# stm32.net
KiCad netlist of a schematic drawn in Altium Designer
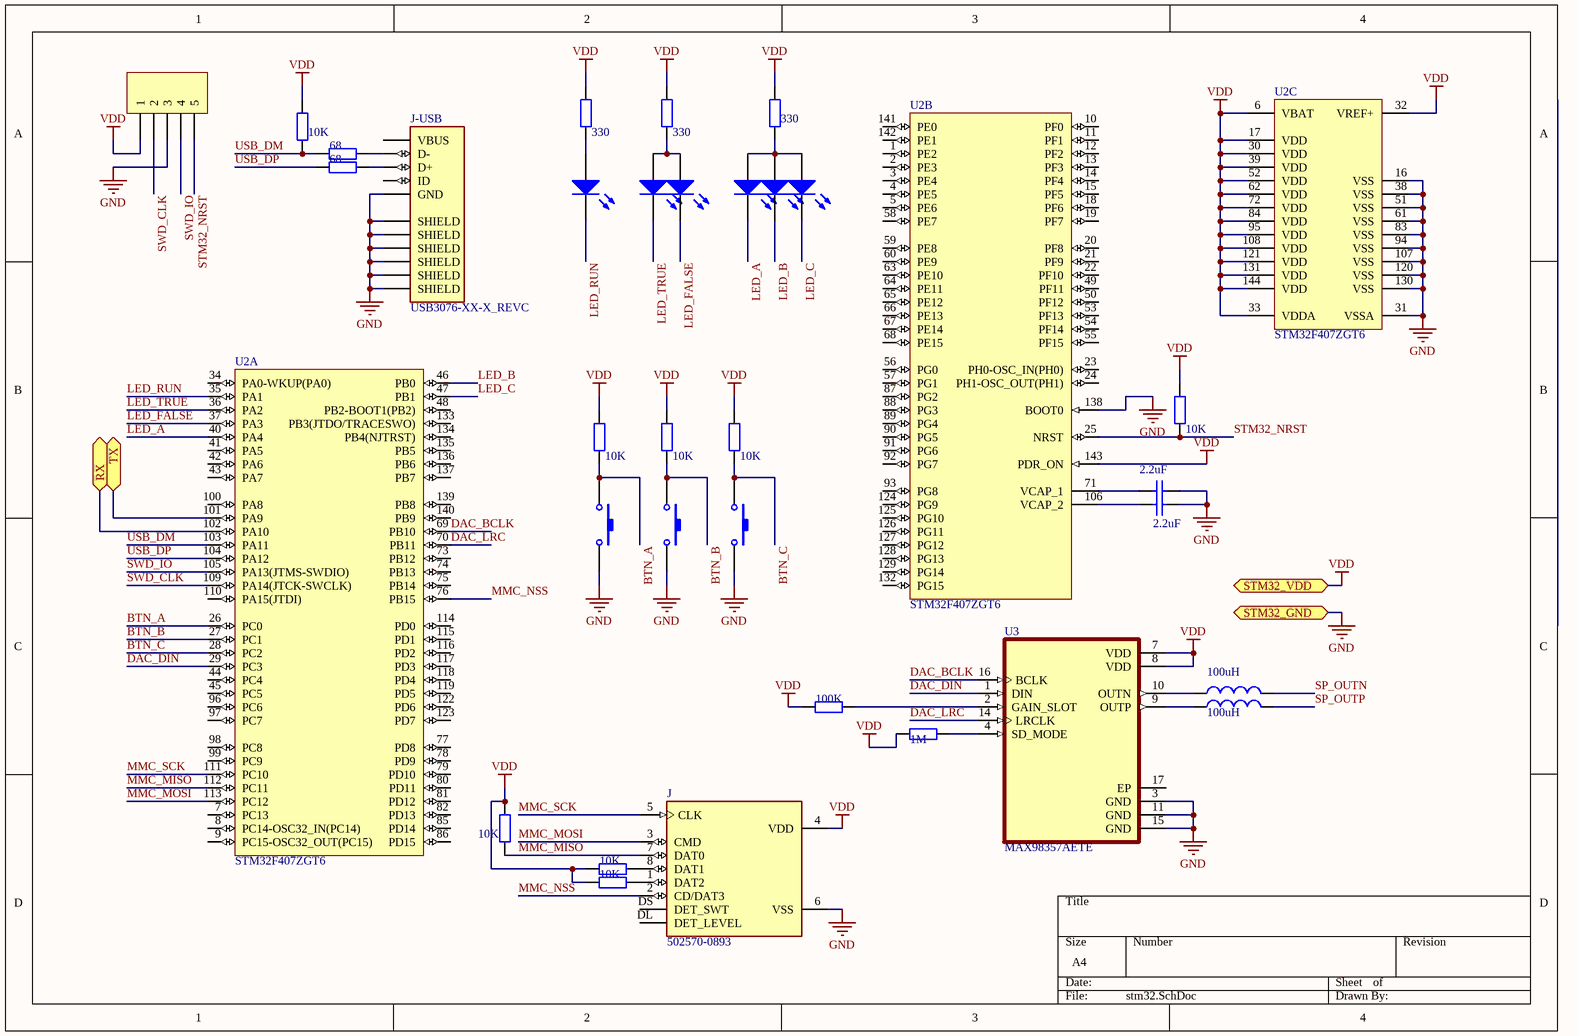
[diagram p0: stm32.SchDoc]

(export (version "E")
  (design (tool "Eeschema 10.0.6"))
  (components
    (comp (ref "D-BTN1")
      (value "LED0")
      (footprint "LED-0")
      (description "Typical INFRARED GaAs LED")
      (fields (field (name "PUBLISHER") "Altium Limited"))
      (libsource (lib "Miscellaneous Devices") (part "LED0"))
    )
    (comp (ref "D-BTN2")
      (value "LED0")
      (footprint "LED-0")
      (description "Typical INFRARED GaAs LED")
      (fields (field (name "PUBLISHER") "Altium Limited"))
      (libsource (lib "Miscellaneous Devices") (part "LED0"))
    )
    (comp (ref "D-BTN3")
      (value "LED0")
      (footprint "LED-0")
      (description "Typical INFRARED GaAs LED")
      (fields (field (name "PUBLISHER") "Altium Limited"))
      (libsource (lib "Miscellaneous Devices") (part "LED0"))
    )
    (comp (ref "D-LED-ANS1")
      (value "LED0")
      (footprint "LED-0")
      (description "Typical INFRARED GaAs LED")
      (fields (field (name "PUBLISHER") "Altium Limited"))
      (libsource (lib "Miscellaneous Devices") (part "LED0"))
    )
    (comp (ref "D-LED-ANS2")
      (value "LED0")
      (footprint "LED-0")
      (description "Typical INFRARED GaAs LED")
      (fields (field (name "PUBLISHER") "Altium Limited"))
      (libsource (lib "Miscellaneous Devices") (part "LED0"))
    )
    (comp (ref "D2")
      (value "LED0")
      (footprint "LED-0")
      (description "Typical INFRARED GaAs LED")
      (fields (field (name "PUBLISHER") "Altium Limited"))
      (libsource (lib "Miscellaneous Devices") (part "LED0"))
    )
    (comp (ref "J")
      (value "502570-0893")
      (footprint "MOLEX_502570-0893")
      (description "10 _8 + 2_ Position Card Connector Secure Digital - microSDâ„¢ Surface Mount, Right Angle Gold")
      (fields (field (name "MF") "Molex"))
      (libsource (lib "MMC-502570-0893") (part "502570-0893"))
    )
    (comp (ref "J-USB")
      (value "USB3076-XX-X_REVC")
      (footprint "GCT_USB3076-XX-X_REVC")
      (description "USB - micro B USB 2.0 Receptacle Connector 5 Position Surface Mount, Right Angle; Through Hole")
      (fields (field (name "MP") "USB3076-30-A") (field (name "MF") "Global Connector Technology"))
      (libsource (lib "USB3076-XX-X_REVC") (part "USB3076-XX-X_REVC"))
    )
    (comp (ref "L-DAC1")
      (value "100uH")
      (footprint "0402-A")
      (description "Inductor")
      (fields (field (name "PUBLISHER") "Altium Limited"))
      (libsource (lib "Miscellaneous Devices") (part "Inductor"))
    )
    (comp (ref "L-DAC2")
      (value "100uH")
      (footprint "0402-A")
      (description "Inductor")
      (fields (field (name "PUBLISHER") "Altium Limited"))
      (libsource (lib "Miscellaneous Devices") (part "Inductor"))
    )
    (comp (ref "P-STM32PROG")
      (value "Header 5")
      (footprint "HDR1X5")
      (description "Header, 5-Pin")
      (fields (field (name "PUBLISHER") "Altium Limited"))
      (libsource (lib "Miscellaneous Connectors") (part "Header 5"))
    )
    (comp (ref "R-BTN1")
      (value "10K")
      (footprint "AXIAL-0.4")
      (description "Resistor")
      (fields (field (name "Comment") "Res2") (field (name "PUBLISHER") "Altium Limited"))
      (libsource (lib "") (part "Res2_1"))
    )
    (comp (ref "R-BTN2")
      (value "10K")
      (footprint "AXIAL-0.4")
      (description "Resistor")
      (fields (field (name "Comment") "Res2") (field (name "PUBLISHER") "Altium Limited"))
      (libsource (lib "") (part "Res2_1"))
    )
    (comp (ref "R-BTN3")
      (value "10K")
      (footprint "AXIAL-0.4")
      (description "Resistor")
      (fields (field (name "Comment") "Res2") (field (name "PUBLISHER") "Altium Limited"))
      (libsource (lib "") (part "Res2_1"))
    )
    (comp (ref "R-DAC1")
      (value "100K")
      (footprint "AXIAL-0.4")
      (description "Resistor")
      (fields (field (name "Comment") "Res2") (field (name "PUBLISHER") "Altium Limited"))
      (libsource (lib "") (part "Res2_2"))
    )
    (comp (ref "R-DAC3")
      (value "1M")
      (footprint "AXIAL-0.4")
      (description "Resistor")
      (fields (field (name "Comment") "Res2") (field (name "PUBLISHER") "Altium Limited"))
      (libsource (lib "") (part "Res2_2"))
    )
    (comp (ref "R-LED-ANS1")
      (value "330")
      (footprint "AXIAL-0.4")
      (description "Resistor")
      (fields (field (name "Comment") "Res2") (field (name "PUBLISHER") "Altium Limited"))
      (libsource (lib "Miscellaneous Devices") (part "Res2"))
    )
    (comp (ref "R-LED-BTN1")
      (value "330")
      (footprint "AXIAL-0.4")
      (description "Resistor")
      (fields (field (name "Comment") "Res2") (field (name "PUBLISHER") "Altium Limited"))
      (libsource (lib "Miscellaneous Devices") (part "Res2"))
    )
    (comp (ref "R-LED-RUN1")
      (value "330")
      (footprint "AXIAL-0.4")
      (description "Resistor")
      (fields (field (name "Comment") "Res2") (field (name "PUBLISHER") "Altium Limited"))
      (libsource (lib "Miscellaneous Devices") (part "Res2"))
    )
    (comp (ref "R-MMC1")
      (value "10K")
      (footprint "AXIAL-0.4")
      (description "Resistor")
      (fields (field (name "Comment") "Res2") (field (name "PUBLISHER") "Altium Limited"))
      (libsource (lib "Miscellaneous Devices") (part "Res2"))
    )
    (comp (ref "R-MMC2")
      (value "10K")
      (footprint "AXIAL-0.4")
      (description "Resistor")
      (fields (field (name "Comment") "Res2") (field (name "PUBLISHER") "Altium Limited"))
      (libsource (lib "") (part "Res2_2"))
    )
    (comp (ref "R-MMC3")
      (value "10K")
      (footprint "AXIAL-0.4")
      (description "Resistor")
      (fields (field (name "Comment") "Res2") (field (name "PUBLISHER") "Altium Limited"))
      (libsource (lib "") (part "Res2_2"))
    )
    (comp (ref "R-STM1")
      (value "10K")
      (footprint "AXIAL-0.4")
      (description "Resistor")
      (fields (field (name "Comment") "Res2") (field (name "PUBLISHER") "Altium Limited"))
      (libsource (lib "Miscellaneous Devices") (part "Res2"))
    )
    (comp (ref "R-USB1")
      (value "10K")
      (footprint "AXIAL-0.4")
      (description "Resistor")
      (fields (field (name "Comment") "Res2") (field (name "PUBLISHER") "Altium Limited"))
      (libsource (lib "Miscellaneous Devices") (part "Res2"))
    )
    (comp (ref "R-USB2")
      (value "68")
      (footprint "AXIAL-0.4")
      (description "Resistor")
      (fields (field (name "Comment") "Res2") (field (name "PUBLISHER") "Altium Limited"))
      (libsource (lib "") (part "Res2_2"))
    )
    (comp (ref "R-USB3")
      (value "68")
      (footprint "AXIAL-0.4")
      (description "Resistor")
      (fields (field (name "Comment") "Res2") (field (name "PUBLISHER") "Altium Limited"))
      (libsource (lib "") (part "Res2_2"))
    )
    (comp (ref "S-BTN1")
      (value "SW-PB")
      (footprint "SPST-2")
      (description "Switch")
      (fields (field (name "PUBLISHER") "Altium Limited"))
      (libsource (lib "Miscellaneous Devices") (part "SW-PB"))
    )
    (comp (ref "S-BTN2")
      (value "SW-PB")
      (footprint "SPST-2")
      (description "Switch")
      (fields (field (name "PUBLISHER") "Altium Limited"))
      (libsource (lib "Miscellaneous Devices") (part "SW-PB"))
    )
    (comp (ref "S-BTN3")
      (value "SW-PB")
      (footprint "SPST-2")
      (description "Switch")
      (fields (field (name "PUBLISHER") "Altium Limited"))
      (libsource (lib "Miscellaneous Devices") (part "SW-PB"))
    )
    (comp (ref "U2")
      (value "STM32F407ZGT6")
      (footprint "STM-LQFP144_N")
      (fields (field (name "MANUFACTURER") "STMicroelectronics"))
      (libsource (lib "STMicroelectronics STM32 F4") (part "STM32F407ZGT6"))
    )
    (comp (ref "U3")
      (value "MAX98357AETE")
      (footprint "QFN50P300X300X80-17N")
      (description "Audio Amp Speaker 1-CH Mono 3.2W Class-D 16-Pin TQFN EP T/R")
      (fields (field (name "MF") "Maxim Integrated"))
      (libsource (lib "MAX98357AETE") (part "MAX98357AETE"))
    )
    (comp (ref "VCAP1")
      (value "2.2uF")
      (footprint "RAD-0.3")
      (description "Capacitor")
      (fields (field (name "Comment") "Cap") (field (name "PUBLISHER") "Altium Limited"))
      (libsource (lib "Miscellaneous Devices") (part "Cap"))
    )
    (comp (ref "VCAP2")
      (value "2.2uF")
      (footprint "RAD-0.3")
      (description "Capacitor")
      (fields (field (name "Comment") "Cap") (field (name "PUBLISHER") "Altium Limited"))
      (libsource (lib "Miscellaneous Devices") (part "Cap"))
    )
  )
  (nets
    (net (code "1") (name "/BTN_A") (class "Default")
      (node (ref "R-BTN1") (pin "2") (pinfunction "2_2") (pintype "passive"))
      (node (ref "S-BTN1") (pin "1") (pinfunction "1_1") (pintype "passive"))
      (node (ref "U2") (pin "26") (pinfunction "PC0_26") (pintype "bidirectional"))
    )
    (net (code "2") (name "/BTN_B") (class "Default")
      (node (ref "R-BTN2") (pin "2") (pinfunction "2_2") (pintype "passive"))
      (node (ref "S-BTN2") (pin "1") (pinfunction "1_1") (pintype "passive"))
      (node (ref "U2") (pin "27") (pinfunction "PC1_27") (pintype "bidirectional"))
    )
    (net (code "3") (name "/BTN_C") (class "Default")
      (node (ref "R-BTN3") (pin "2") (pinfunction "2_2") (pintype "passive"))
      (node (ref "S-BTN3") (pin "1") (pinfunction "1_1") (pintype "passive"))
      (node (ref "U2") (pin "28") (pinfunction "PC2_28") (pintype "bidirectional"))
    )
    (net (code "4") (name "/DAC_BCLK") (class "Default")
      (node (ref "U2") (pin "69") (pinfunction "PB10_69") (pintype "bidirectional"))
      (node (ref "U3") (pin "16") (pinfunction "BCLK_16") (pintype "input"))
    )
    (net (code "5") (name "/DAC_DIN") (class "Default")
      (node (ref "U2") (pin "29") (pinfunction "PC3_29") (pintype "bidirectional"))
      (node (ref "U3") (pin "1") (pinfunction "DIN_1") (pintype "input"))
    )
    (net (code "6") (name "/DAC_LRC") (class "Default")
      (node (ref "U2") (pin "70") (pinfunction "PB11_70") (pintype "bidirectional"))
      (node (ref "U3") (pin "14") (pinfunction "LRCLK_14") (pintype "input"))
    )
    (net (code "7") (name "/LED_A") (class "Default")
      (node (ref "D-BTN1") (pin "2") (pinfunction "K_2") (pintype "passive"))
      (node (ref "U2") (pin "40") (pinfunction "PA4_40") (pintype "bidirectional"))
    )
    (net (code "8") (name "/LED_B") (class "Default")
      (node (ref "D-BTN2") (pin "2") (pinfunction "K_2") (pintype "passive"))
      (node (ref "U2") (pin "46") (pinfunction "PB0_46") (pintype "bidirectional"))
    )
    (net (code "9") (name "/LED_C") (class "Default")
      (node (ref "D-BTN3") (pin "2") (pinfunction "K_2") (pintype "passive"))
      (node (ref "U2") (pin "47") (pinfunction "PB1_47") (pintype "bidirectional"))
    )
    (net (code "10") (name "/LED_FALSE") (class "Default")
      (node (ref "D-LED-ANS2") (pin "2") (pinfunction "K_2") (pintype "passive"))
      (node (ref "U2") (pin "37") (pinfunction "PA3_37") (pintype "bidirectional"))
    )
    (net (code "11") (name "/LED_RUN") (class "Default")
      (node (ref "D2") (pin "2") (pinfunction "K_2") (pintype "passive"))
      (node (ref "U2") (pin "35") (pinfunction "PA1_35") (pintype "bidirectional"))
    )
    (net (code "12") (name "/LED_TRUE") (class "Default")
      (node (ref "D-LED-ANS1") (pin "2") (pinfunction "K_2") (pintype "passive"))
      (node (ref "U2") (pin "36") (pinfunction "PA2_36") (pintype "bidirectional"))
    )
    (net (code "13") (name "/MMC_MISO") (class "Default")
      (node (ref "J") (pin "7") (pinfunction "DAT0_7") (pintype "bidirectional"))
      (node (ref "R-MMC1") (pin "1") (pinfunction "1_1") (pintype "passive"))
      (node (ref "U2") (pin "112") (pinfunction "PC11_112") (pintype "bidirectional"))
    )
    (net (code "14") (name "/MMC_MOSI") (class "Default")
      (node (ref "J") (pin "3") (pinfunction "CMD_3") (pintype "bidirectional"))
      (node (ref "U2") (pin "113") (pinfunction "PC12_113") (pintype "bidirectional"))
    )
    (net (code "15") (name "/MMC_NSS") (class "Default")
      (node (ref "J") (pin "2") (pinfunction "CD/DAT3_2") (pintype "bidirectional"))
      (node (ref "U2") (pin "76") (pinfunction "PB15_76") (pintype "bidirectional"))
    )
    (net (code "16") (name "/MMC_SCK") (class "Default")
      (node (ref "J") (pin "5") (pinfunction "CLK_5") (pintype "input"))
      (node (ref "U2") (pin "111") (pinfunction "PC10_111") (pintype "bidirectional"))
    )
    (net (code "17") (name "/RX") (class "Default")
      (node (ref "U2") (pin "102") (pinfunction "PA10_102") (pintype "bidirectional"))
    )
    (net (code "18") (name "/SP_OUTN") (class "Default")
      (node (ref "L-DAC1") (pin "2") (pinfunction "2_2") (pintype "passive"))
    )
    (net (code "19") (name "/SP_OUTP") (class "Default")
      (node (ref "L-DAC2") (pin "2") (pinfunction "2_2") (pintype "passive"))
    )
    (net (code "20") (name "/STM32_NRST") (class "Default")
      (node (ref "P-STM32PROG") (pin "5") (pinfunction "5_5") (pintype "passive"))
      (node (ref "R-STM1") (pin "1") (pinfunction "1_1") (pintype "passive"))
      (node (ref "U2") (pin "25") (pinfunction "NRST_25") (pintype "bidirectional"))
    )
    (net (code "21") (name "/SWD_CLK") (class "Default")
      (node (ref "P-STM32PROG") (pin "2") (pinfunction "2_2") (pintype "passive"))
      (node (ref "U2") (pin "109") (pinfunction "PA14(JTCK-SWCLK)_109") (pintype "bidirectional"))
    )
    (net (code "22") (name "/SWD_IO") (class "Default")
      (node (ref "P-STM32PROG") (pin "4") (pinfunction "4_4") (pintype "passive"))
      (node (ref "U2") (pin "105") (pinfunction "PA13(JTMS-SWDIO)_105") (pintype "bidirectional"))
    )
    (net (code "23") (name "/TX") (class "Default")
      (node (ref "U2") (pin "101") (pinfunction "PA9_101") (pintype "bidirectional"))
    )
    (net (code "24") (name "/USB_DM") (class "Default")
      (node (ref "R-USB1") (pin "1") (pinfunction "1_1") (pintype "passive"))
      (node (ref "R-USB2") (pin "1") (pinfunction "1_1") (pintype "passive"))
      (node (ref "U2") (pin "103") (pinfunction "PA11_103") (pintype "bidirectional"))
    )
    (net (code "25") (name "/USB_DP") (class "Default")
      (node (ref "R-USB3") (pin "1") (pinfunction "1_1") (pintype "passive"))
      (node (ref "U2") (pin "104") (pinfunction "PA12_104") (pintype "bidirectional"))
    )
    (net (code "26") (name "GND") (class "Default")
      (node (ref "J") (pin "6") (pinfunction "VSS_6") (pintype "power_in"))
      (node (ref "J-USB") (pin "10") (pinfunction "SHIELD_10") (pintype "power_in"))
      (node (ref "J-USB") (pin "11") (pinfunction "SHIELD_11") (pintype "power_in"))
      (node (ref "J-USB") (pin "5") (pinfunction "GND_5") (pintype "power_in"))
      (node (ref "J-USB") (pin "6") (pinfunction "SHIELD_6") (pintype "power_in"))
      (node (ref "J-USB") (pin "7") (pinfunction "SHIELD_7") (pintype "power_in"))
      (node (ref "J-USB") (pin "8") (pinfunction "SHIELD_8") (pintype "power_in"))
      (node (ref "J-USB") (pin "9") (pinfunction "SHIELD_9") (pintype "power_in"))
      (node (ref "P-STM32PROG") (pin "3") (pinfunction "3_3") (pintype "passive"))
      (node (ref "S-BTN1") (pin "2") (pinfunction "2_2") (pintype "passive"))
      (node (ref "S-BTN2") (pin "2") (pinfunction "2_2") (pintype "passive"))
      (node (ref "S-BTN3") (pin "2") (pinfunction "2_2") (pintype "passive"))
      (node (ref "U2") (pin "107") (pinfunction "VSS_107") (pintype "power_in"))
      (node (ref "U2") (pin "120") (pinfunction "VSS_120") (pintype "power_in"))
      (node (ref "U2") (pin "130") (pinfunction "VSS_130") (pintype "power_in"))
      (node (ref "U2") (pin "138") (pinfunction "BOOT0_138") (pintype "input"))
      (node (ref "U2") (pin "16") (pinfunction "VSS_16") (pintype "power_in"))
      (node (ref "U2") (pin "31") (pinfunction "VSSA_31") (pintype "power_in"))
      (node (ref "U2") (pin "38") (pinfunction "VSS_38") (pintype "power_in"))
      (node (ref "U2") (pin "51") (pinfunction "VSS_51") (pintype "power_in"))
      (node (ref "U2") (pin "61") (pinfunction "VSS_61") (pintype "power_in"))
      (node (ref "U2") (pin "83") (pinfunction "VSS_83") (pintype "power_in"))
      (node (ref "U2") (pin "94") (pinfunction "VSS_94") (pintype "power_in"))
      (node (ref "U3") (pin "11") (pinfunction "GND_11") (pintype "power_in"))
      (node (ref "U3") (pin "15") (pinfunction "GND_15") (pintype "power_in"))
      (node (ref "U3") (pin "3") (pinfunction "GND_3") (pintype "power_in"))
      (node (ref "VCAP1") (pin "2") (pinfunction "2_2") (pintype "passive"))
      (node (ref "VCAP2") (pin "2") (pinfunction "2_2") (pintype "passive"))
    )
    (net (code "27") (name "Net-(D-BTN1-A)") (class "Default")
      (node (ref "D-BTN1") (pin "1") (pinfunction "A_1") (pintype "passive"))
      (node (ref "D-BTN2") (pin "1") (pinfunction "A_1") (pintype "passive"))
      (node (ref "D-BTN3") (pin "1") (pinfunction "A_1") (pintype "passive"))
      (node (ref "R-LED-BTN1") (pin "1") (pinfunction "1_1") (pintype "passive"))
    )
    (net (code "28") (name "Net-(D-LED-ANS1-A)") (class "Default")
      (node (ref "D-LED-ANS1") (pin "1") (pinfunction "A_1") (pintype "passive"))
      (node (ref "D-LED-ANS2") (pin "1") (pinfunction "A_1") (pintype "passive"))
      (node (ref "R-LED-ANS1") (pin "1") (pinfunction "1_1") (pintype "passive"))
    )
    (net (code "29") (name "Net-(D2-A)") (class "Default")
      (node (ref "D2") (pin "1") (pinfunction "A_1") (pintype "passive"))
      (node (ref "R-LED-RUN1") (pin "1") (pinfunction "1_1") (pintype "passive"))
    )
    (net (code "30") (name "Net-(J-DAT1)") (class "Default")
      (node (ref "J") (pin "8") (pinfunction "DAT1_8") (pintype "bidirectional"))
      (node (ref "R-MMC2") (pin "2") (pinfunction "2_2") (pintype "passive"))
    )
    (net (code "31") (name "Net-(J-DAT2)") (class "Default")
      (node (ref "J") (pin "1") (pinfunction "DAT2_1") (pintype "bidirectional"))
      (node (ref "R-MMC3") (pin "2") (pinfunction "2_2") (pintype "passive"))
    )
    (net (code "32") (name "Net-(J-USB-D+)") (class "Default")
      (node (ref "J-USB") (pin "3") (pinfunction "D+_3") (pintype "bidirectional"))
      (node (ref "R-USB3") (pin "2") (pinfunction "2_2") (pintype "passive"))
    )
    (net (code "33") (name "Net-(J-USB-D-)") (class "Default")
      (node (ref "J-USB") (pin "2") (pinfunction "D-_2") (pintype "bidirectional"))
      (node (ref "R-USB2") (pin "2") (pinfunction "2_2") (pintype "passive"))
    )
    (net (code "34") (name "Net-(U2B-VCAP_1)") (class "Default")
      (node (ref "U2") (pin "71") (pinfunction "VCAP_1_71") (pintype "power_in"))
      (node (ref "VCAP1") (pin "1") (pinfunction "1_1") (pintype "passive"))
    )
    (net (code "35") (name "Net-(U2B-VCAP_2)") (class "Default")
      (node (ref "U2") (pin "106") (pinfunction "VCAP_2_106") (pintype "power_in"))
      (node (ref "VCAP2") (pin "1") (pinfunction "1_1") (pintype "passive"))
    )
    (net (code "36") (name "Net-(U3-GAIN_SLOT)") (class "Default")
      (node (ref "R-DAC1") (pin "2") (pinfunction "2_2") (pintype "passive"))
      (node (ref "U3") (pin "2") (pinfunction "GAIN_SLOT_2") (pintype "input"))
    )
    (net (code "37") (name "Net-(U3-OUTN)") (class "Default")
      (node (ref "L-DAC1") (pin "1") (pinfunction "1_1") (pintype "passive"))
      (node (ref "U3") (pin "10") (pinfunction "OUTN_10") (pintype "output"))
    )
    (net (code "38") (name "Net-(U3-OUTP)") (class "Default")
      (node (ref "L-DAC2") (pin "1") (pinfunction "1_1") (pintype "passive"))
      (node (ref "U3") (pin "9") (pinfunction "OUTP_9") (pintype "output"))
    )
    (net (code "39") (name "Net-(U3-SD_MODE)") (class "Default")
      (node (ref "R-DAC3") (pin "2") (pinfunction "2_2") (pintype "passive"))
      (node (ref "U3") (pin "4") (pinfunction "SD_MODE_4") (pintype "input"))
    )
    (net (code "40") (name "VDD") (class "Default")
      (node (ref "J") (pin "4") (pinfunction "VDD_4") (pintype "power_in"))
      (node (ref "P-STM32PROG") (pin "1") (pinfunction "1_1") (pintype "passive"))
      (node (ref "R-BTN1") (pin "1") (pinfunction "1_1") (pintype "passive"))
      (node (ref "R-BTN2") (pin "1") (pinfunction "1_1") (pintype "passive"))
      (node (ref "R-BTN3") (pin "1") (pinfunction "1_1") (pintype "passive"))
      (node (ref "R-DAC1") (pin "1") (pinfunction "1_1") (pintype "passive"))
      (node (ref "R-DAC3") (pin "1") (pinfunction "1_1") (pintype "passive"))
      (node (ref "R-LED-ANS1") (pin "2") (pinfunction "2_2") (pintype "passive"))
      (node (ref "R-LED-BTN1") (pin "2") (pinfunction "2_2") (pintype "passive"))
      (node (ref "R-LED-RUN1") (pin "2") (pinfunction "2_2") (pintype "passive"))
      (node (ref "R-MMC1") (pin "2") (pinfunction "2_2") (pintype "passive"))
      (node (ref "R-MMC2") (pin "1") (pinfunction "1_1") (pintype "passive"))
      (node (ref "R-MMC3") (pin "1") (pinfunction "1_1") (pintype "passive"))
      (node (ref "R-STM1") (pin "2") (pinfunction "2_2") (pintype "passive"))
      (node (ref "R-USB1") (pin "2") (pinfunction "2_2") (pintype "passive"))
      (node (ref "U2") (pin "108") (pinfunction "VDD_108") (pintype "power_in"))
      (node (ref "U2") (pin "121") (pinfunction "VDD_121") (pintype "power_in"))
      (node (ref "U2") (pin "131") (pinfunction "VDD_131") (pintype "power_in"))
      (node (ref "U2") (pin "143") (pinfunction "PDR_ON_143") (pintype "input"))
      (node (ref "U2") (pin "144") (pinfunction "VDD_144") (pintype "power_in"))
      (node (ref "U2") (pin "17") (pinfunction "VDD_17") (pintype "power_in"))
      (node (ref "U2") (pin "30") (pinfunction "VDD_30") (pintype "power_in"))
      (node (ref "U2") (pin "32") (pinfunction "VREF+_32") (pintype "power_in"))
      (node (ref "U2") (pin "33") (pinfunction "VDDA_33") (pintype "power_in"))
      (node (ref "U2") (pin "39") (pinfunction "VDD_39") (pintype "power_in"))
      (node (ref "U2") (pin "52") (pinfunction "VDD_52") (pintype "power_in"))
      (node (ref "U2") (pin "6") (pinfunction "VBAT_6") (pintype "power_in"))
      (node (ref "U2") (pin "62") (pinfunction "VDD_62") (pintype "power_in"))
      (node (ref "U2") (pin "72") (pinfunction "VDD_72") (pintype "power_in"))
      (node (ref "U2") (pin "84") (pinfunction "VDD_84") (pintype "power_in"))
      (node (ref "U2") (pin "95") (pinfunction "VDD_95") (pintype "power_in"))
      (node (ref "U3") (pin "7") (pinfunction "VDD_7") (pintype "power_in"))
      (node (ref "U3") (pin "8") (pinfunction "VDD_8") (pintype "power_in"))
    )
    (net (code "41") (name "unconnected-(J-DET_LEVEL-PadDL)") (class "Default")
      (node (ref "J") (pin "DL") (pinfunction "DET_LEVEL_DL") (pintype "passive"))
    )
    (net (code "42") (name "unconnected-(J-DET_SWT-PadDS)") (class "Default")
      (node (ref "J") (pin "DS") (pinfunction "DET_SWT_DS") (pintype "passive"))
    )
    (net (code "43") (name "unconnected-(J-USB-ID-Pad4)") (class "Default")
      (node (ref "J-USB") (pin "4") (pinfunction "ID_4") (pintype "bidirectional"))
    )
    (net (code "44") (name "unconnected-(J-USB-VBUS-Pad1)") (class "Default")
      (node (ref "J-USB") (pin "1") (pinfunction "VBUS_1") (pintype "power_in"))
    )
    (net (code "45") (name "unconnected-(U2A-PA0-WKUP(PA0)-Pad34)") (class "Default")
      (node (ref "U2") (pin "34") (pinfunction "PA0-WKUP(PA0)_34") (pintype "bidirectional"))
    )
    (net (code "46") (name "unconnected-(U2A-PA5-Pad41)") (class "Default")
      (node (ref "U2") (pin "41") (pinfunction "PA5_41") (pintype "bidirectional"))
    )
    (net (code "47") (name "unconnected-(U2A-PA6-Pad42)") (class "Default")
      (node (ref "U2") (pin "42") (pinfunction "PA6_42") (pintype "bidirectional"))
    )
    (net (code "48") (name "unconnected-(U2A-PA7-Pad43)") (class "Default")
      (node (ref "U2") (pin "43") (pinfunction "PA7_43") (pintype "bidirectional"))
    )
    (net (code "49") (name "unconnected-(U2A-PA8-Pad100)") (class "Default")
      (node (ref "U2") (pin "100") (pinfunction "PA8_100") (pintype "bidirectional"))
    )
    (net (code "50") (name "unconnected-(U2A-PA15(JTDI)-Pad110)") (class "Default")
      (node (ref "U2") (pin "110") (pinfunction "PA15(JTDI)_110") (pintype "bidirectional"))
    )
    (net (code "51") (name "unconnected-(U2A-PB2-BOOT1(PB2)-Pad48)") (class "Default")
      (node (ref "U2") (pin "48") (pinfunction "PB2-BOOT1(PB2)_48") (pintype "bidirectional"))
    )
    (net (code "52") (name "unconnected-(U2A-PB3(JTDO{slash}TRACESWO)-Pad133)") (class "Default")
      (node (ref "U2") (pin "133") (pinfunction "PB3(JTDO/TRACESWO)_133") (pintype "bidirectional"))
    )
    (net (code "53") (name "unconnected-(U2A-PB4(NJTRST)-Pad134)") (class "Default")
      (node (ref "U2") (pin "134") (pinfunction "PB4(NJTRST)_134") (pintype "bidirectional"))
    )
    (net (code "54") (name "unconnected-(U2A-PB5-Pad135)") (class "Default")
      (node (ref "U2") (pin "135") (pinfunction "PB5_135") (pintype "bidirectional"))
    )
    (net (code "55") (name "unconnected-(U2A-PB6-Pad136)") (class "Default")
      (node (ref "U2") (pin "136") (pinfunction "PB6_136") (pintype "bidirectional"))
    )
    (net (code "56") (name "unconnected-(U2A-PB7-Pad137)") (class "Default")
      (node (ref "U2") (pin "137") (pinfunction "PB7_137") (pintype "bidirectional"))
    )
    (net (code "57") (name "unconnected-(U2A-PB8-Pad139)") (class "Default")
      (node (ref "U2") (pin "139") (pinfunction "PB8_139") (pintype "bidirectional"))
    )
    (net (code "58") (name "unconnected-(U2A-PB9-Pad140)") (class "Default")
      (node (ref "U2") (pin "140") (pinfunction "PB9_140") (pintype "bidirectional"))
    )
    (net (code "59") (name "unconnected-(U2A-PB12-Pad73)") (class "Default")
      (node (ref "U2") (pin "73") (pinfunction "PB12_73") (pintype "bidirectional"))
    )
    (net (code "60") (name "unconnected-(U2A-PB13-Pad74)") (class "Default")
      (node (ref "U2") (pin "74") (pinfunction "PB13_74") (pintype "bidirectional"))
    )
    (net (code "61") (name "unconnected-(U2A-PB14-Pad75)") (class "Default")
      (node (ref "U2") (pin "75") (pinfunction "PB14_75") (pintype "bidirectional"))
    )
    (net (code "62") (name "unconnected-(U2A-PC4-Pad44)") (class "Default")
      (node (ref "U2") (pin "44") (pinfunction "PC4_44") (pintype "bidirectional"))
    )
    (net (code "63") (name "unconnected-(U2A-PC5-Pad45)") (class "Default")
      (node (ref "U2") (pin "45") (pinfunction "PC5_45") (pintype "bidirectional"))
    )
    (net (code "64") (name "unconnected-(U2A-PC6-Pad96)") (class "Default")
      (node (ref "U2") (pin "96") (pinfunction "PC6_96") (pintype "bidirectional"))
    )
    (net (code "65") (name "unconnected-(U2A-PC7-Pad97)") (class "Default")
      (node (ref "U2") (pin "97") (pinfunction "PC7_97") (pintype "bidirectional"))
    )
    (net (code "66") (name "unconnected-(U2A-PC8-Pad98)") (class "Default")
      (node (ref "U2") (pin "98") (pinfunction "PC8_98") (pintype "bidirectional"))
    )
    (net (code "67") (name "unconnected-(U2A-PC9-Pad99)") (class "Default")
      (node (ref "U2") (pin "99") (pinfunction "PC9_99") (pintype "bidirectional"))
    )
    (net (code "68") (name "unconnected-(U2A-PC13-Pad7)") (class "Default")
      (node (ref "U2") (pin "7") (pinfunction "PC13_7") (pintype "bidirectional"))
    )
    (net (code "69") (name "unconnected-(U2A-PC14-OSC32_IN(PC14)-Pad8)") (class "Default")
      (node (ref "U2") (pin "8") (pinfunction "PC14-OSC32_IN(PC14)_8") (pintype "bidirectional"))
    )
    (net (code "70") (name "unconnected-(U2A-PC15-OSC32_OUT(PC15)-Pad9)") (class "Default")
      (node (ref "U2") (pin "9") (pinfunction "PC15-OSC32_OUT(PC15)_9") (pintype "bidirectional"))
    )
    (net (code "71") (name "unconnected-(U2A-PD0-Pad114)") (class "Default")
      (node (ref "U2") (pin "114") (pinfunction "PD0_114") (pintype "bidirectional"))
    )
    (net (code "72") (name "unconnected-(U2A-PD1-Pad115)") (class "Default")
      (node (ref "U2") (pin "115") (pinfunction "PD1_115") (pintype "bidirectional"))
    )
    (net (code "73") (name "unconnected-(U2A-PD2-Pad116)") (class "Default")
      (node (ref "U2") (pin "116") (pinfunction "PD2_116") (pintype "bidirectional"))
    )
    (net (code "74") (name "unconnected-(U2A-PD3-Pad117)") (class "Default")
      (node (ref "U2") (pin "117") (pinfunction "PD3_117") (pintype "bidirectional"))
    )
    (net (code "75") (name "unconnected-(U2A-PD4-Pad118)") (class "Default")
      (node (ref "U2") (pin "118") (pinfunction "PD4_118") (pintype "bidirectional"))
    )
    (net (code "76") (name "unconnected-(U2A-PD5-Pad119)") (class "Default")
      (node (ref "U2") (pin "119") (pinfunction "PD5_119") (pintype "bidirectional"))
    )
    (net (code "77") (name "unconnected-(U2A-PD6-Pad122)") (class "Default")
      (node (ref "U2") (pin "122") (pinfunction "PD6_122") (pintype "bidirectional"))
    )
    (net (code "78") (name "unconnected-(U2A-PD7-Pad123)") (class "Default")
      (node (ref "U2") (pin "123") (pinfunction "PD7_123") (pintype "bidirectional"))
    )
    (net (code "79") (name "unconnected-(U2A-PD8-Pad77)") (class "Default")
      (node (ref "U2") (pin "77") (pinfunction "PD8_77") (pintype "bidirectional"))
    )
    (net (code "80") (name "unconnected-(U2A-PD9-Pad78)") (class "Default")
      (node (ref "U2") (pin "78") (pinfunction "PD9_78") (pintype "bidirectional"))
    )
    (net (code "81") (name "unconnected-(U2A-PD10-Pad79)") (class "Default")
      (node (ref "U2") (pin "79") (pinfunction "PD10_79") (pintype "bidirectional"))
    )
    (net (code "82") (name "unconnected-(U2A-PD11-Pad80)") (class "Default")
      (node (ref "U2") (pin "80") (pinfunction "PD11_80") (pintype "bidirectional"))
    )
    (net (code "83") (name "unconnected-(U2A-PD12-Pad81)") (class "Default")
      (node (ref "U2") (pin "81") (pinfunction "PD12_81") (pintype "bidirectional"))
    )
    (net (code "84") (name "unconnected-(U2A-PD13-Pad82)") (class "Default")
      (node (ref "U2") (pin "82") (pinfunction "PD13_82") (pintype "bidirectional"))
    )
    (net (code "85") (name "unconnected-(U2A-PD14-Pad85)") (class "Default")
      (node (ref "U2") (pin "85") (pinfunction "PD14_85") (pintype "bidirectional"))
    )
    (net (code "86") (name "unconnected-(U2A-PD15-Pad86)") (class "Default")
      (node (ref "U2") (pin "86") (pinfunction "PD15_86") (pintype "bidirectional"))
    )
    (net (code "87") (name "unconnected-(U2B-PE0-Pad141)") (class "Default")
      (node (ref "U2") (pin "141") (pinfunction "PE0_141") (pintype "bidirectional"))
    )
    (net (code "88") (name "unconnected-(U2B-PE1-Pad142)") (class "Default")
      (node (ref "U2") (pin "142") (pinfunction "PE1_142") (pintype "bidirectional"))
    )
    (net (code "89") (name "unconnected-(U2B-PE2-Pad1)") (class "Default")
      (node (ref "U2") (pin "1") (pinfunction "PE2_1") (pintype "bidirectional"))
    )
    (net (code "90") (name "unconnected-(U2B-PE3-Pad2)") (class "Default")
      (node (ref "U2") (pin "2") (pinfunction "PE3_2") (pintype "bidirectional"))
    )
    (net (code "91") (name "unconnected-(U2B-PE4-Pad3)") (class "Default")
      (node (ref "U2") (pin "3") (pinfunction "PE4_3") (pintype "bidirectional"))
    )
    (net (code "92") (name "unconnected-(U2B-PE5-Pad4)") (class "Default")
      (node (ref "U2") (pin "4") (pinfunction "PE5_4") (pintype "bidirectional"))
    )
    (net (code "93") (name "unconnected-(U2B-PE6-Pad5)") (class "Default")
      (node (ref "U2") (pin "5") (pinfunction "PE6_5") (pintype "bidirectional"))
    )
    (net (code "94") (name "unconnected-(U2B-PE7-Pad58)") (class "Default")
      (node (ref "U2") (pin "58") (pinfunction "PE7_58") (pintype "bidirectional"))
    )
    (net (code "95") (name "unconnected-(U2B-PE8-Pad59)") (class "Default")
      (node (ref "U2") (pin "59") (pinfunction "PE8_59") (pintype "bidirectional"))
    )
    (net (code "96") (name "unconnected-(U2B-PE9-Pad60)") (class "Default")
      (node (ref "U2") (pin "60") (pinfunction "PE9_60") (pintype "bidirectional"))
    )
    (net (code "97") (name "unconnected-(U2B-PE10-Pad63)") (class "Default")
      (node (ref "U2") (pin "63") (pinfunction "PE10_63") (pintype "bidirectional"))
    )
    (net (code "98") (name "unconnected-(U2B-PE11-Pad64)") (class "Default")
      (node (ref "U2") (pin "64") (pinfunction "PE11_64") (pintype "bidirectional"))
    )
    (net (code "99") (name "unconnected-(U2B-PE12-Pad65)") (class "Default")
      (node (ref "U2") (pin "65") (pinfunction "PE12_65") (pintype "bidirectional"))
    )
    (net (code "100") (name "unconnected-(U2B-PE13-Pad66)") (class "Default")
      (node (ref "U2") (pin "66") (pinfunction "PE13_66") (pintype "bidirectional"))
    )
    (net (code "101") (name "unconnected-(U2B-PE14-Pad67)") (class "Default")
      (node (ref "U2") (pin "67") (pinfunction "PE14_67") (pintype "bidirectional"))
    )
    (net (code "102") (name "unconnected-(U2B-PE15-Pad68)") (class "Default")
      (node (ref "U2") (pin "68") (pinfunction "PE15_68") (pintype "bidirectional"))
    )
    (net (code "103") (name "unconnected-(U2B-PF0-Pad10)") (class "Default")
      (node (ref "U2") (pin "10") (pinfunction "PF0_10") (pintype "bidirectional"))
    )
    (net (code "104") (name "unconnected-(U2B-PF1-Pad11)") (class "Default")
      (node (ref "U2") (pin "11") (pinfunction "PF1_11") (pintype "bidirectional"))
    )
    (net (code "105") (name "unconnected-(U2B-PF2-Pad12)") (class "Default")
      (node (ref "U2") (pin "12") (pinfunction "PF2_12") (pintype "bidirectional"))
    )
    (net (code "106") (name "unconnected-(U2B-PF3-Pad13)") (class "Default")
      (node (ref "U2") (pin "13") (pinfunction "PF3_13") (pintype "bidirectional"))
    )
    (net (code "107") (name "unconnected-(U2B-PF4-Pad14)") (class "Default")
      (node (ref "U2") (pin "14") (pinfunction "PF4_14") (pintype "bidirectional"))
    )
    (net (code "108") (name "unconnected-(U2B-PF5-Pad15)") (class "Default")
      (node (ref "U2") (pin "15") (pinfunction "PF5_15") (pintype "bidirectional"))
    )
    (net (code "109") (name "unconnected-(U2B-PF6-Pad18)") (class "Default")
      (node (ref "U2") (pin "18") (pinfunction "PF6_18") (pintype "bidirectional"))
    )
    (net (code "110") (name "unconnected-(U2B-PF7-Pad19)") (class "Default")
      (node (ref "U2") (pin "19") (pinfunction "PF7_19") (pintype "bidirectional"))
    )
    (net (code "111") (name "unconnected-(U2B-PF8-Pad20)") (class "Default")
      (node (ref "U2") (pin "20") (pinfunction "PF8_20") (pintype "bidirectional"))
    )
    (net (code "112") (name "unconnected-(U2B-PF9-Pad21)") (class "Default")
      (node (ref "U2") (pin "21") (pinfunction "PF9_21") (pintype "bidirectional"))
    )
    (net (code "113") (name "unconnected-(U2B-PF10-Pad22)") (class "Default")
      (node (ref "U2") (pin "22") (pinfunction "PF10_22") (pintype "bidirectional"))
    )
    (net (code "114") (name "unconnected-(U2B-PF11-Pad49)") (class "Default")
      (node (ref "U2") (pin "49") (pinfunction "PF11_49") (pintype "bidirectional"))
    )
    (net (code "115") (name "unconnected-(U2B-PF12-Pad50)") (class "Default")
      (node (ref "U2") (pin "50") (pinfunction "PF12_50") (pintype "bidirectional"))
    )
    (net (code "116") (name "unconnected-(U2B-PF13-Pad53)") (class "Default")
      (node (ref "U2") (pin "53") (pinfunction "PF13_53") (pintype "bidirectional"))
    )
    (net (code "117") (name "unconnected-(U2B-PF14-Pad54)") (class "Default")
      (node (ref "U2") (pin "54") (pinfunction "PF14_54") (pintype "bidirectional"))
    )
    (net (code "118") (name "unconnected-(U2B-PF15-Pad55)") (class "Default")
      (node (ref "U2") (pin "55") (pinfunction "PF15_55") (pintype "bidirectional"))
    )
    (net (code "119") (name "unconnected-(U2B-PG0-Pad56)") (class "Default")
      (node (ref "U2") (pin "56") (pinfunction "PG0_56") (pintype "bidirectional"))
    )
    (net (code "120") (name "unconnected-(U2B-PG1-Pad57)") (class "Default")
      (node (ref "U2") (pin "57") (pinfunction "PG1_57") (pintype "bidirectional"))
    )
    (net (code "121") (name "unconnected-(U2B-PG2-Pad87)") (class "Default")
      (node (ref "U2") (pin "87") (pinfunction "PG2_87") (pintype "bidirectional"))
    )
    (net (code "122") (name "unconnected-(U2B-PG3-Pad88)") (class "Default")
      (node (ref "U2") (pin "88") (pinfunction "PG3_88") (pintype "bidirectional"))
    )
    (net (code "123") (name "unconnected-(U2B-PG4-Pad89)") (class "Default")
      (node (ref "U2") (pin "89") (pinfunction "PG4_89") (pintype "bidirectional"))
    )
    (net (code "124") (name "unconnected-(U2B-PG5-Pad90)") (class "Default")
      (node (ref "U2") (pin "90") (pinfunction "PG5_90") (pintype "bidirectional"))
    )
    (net (code "125") (name "unconnected-(U2B-PG6-Pad91)") (class "Default")
      (node (ref "U2") (pin "91") (pinfunction "PG6_91") (pintype "bidirectional"))
    )
    (net (code "126") (name "unconnected-(U2B-PG7-Pad92)") (class "Default")
      (node (ref "U2") (pin "92") (pinfunction "PG7_92") (pintype "bidirectional"))
    )
    (net (code "127") (name "unconnected-(U2B-PG8-Pad93)") (class "Default")
      (node (ref "U2") (pin "93") (pinfunction "PG8_93") (pintype "bidirectional"))
    )
    (net (code "128") (name "unconnected-(U2B-PG9-Pad124)") (class "Default")
      (node (ref "U2") (pin "124") (pinfunction "PG9_124") (pintype "bidirectional"))
    )
    (net (code "129") (name "unconnected-(U2B-PG10-Pad125)") (class "Default")
      (node (ref "U2") (pin "125") (pinfunction "PG10_125") (pintype "bidirectional"))
    )
    (net (code "130") (name "unconnected-(U2B-PG11-Pad126)") (class "Default")
      (node (ref "U2") (pin "126") (pinfunction "PG11_126") (pintype "bidirectional"))
    )
    (net (code "131") (name "unconnected-(U2B-PG12-Pad127)") (class "Default")
      (node (ref "U2") (pin "127") (pinfunction "PG12_127") (pintype "bidirectional"))
    )
    (net (code "132") (name "unconnected-(U2B-PG13-Pad128)") (class "Default")
      (node (ref "U2") (pin "128") (pinfunction "PG13_128") (pintype "bidirectional"))
    )
    (net (code "133") (name "unconnected-(U2B-PG14-Pad129)") (class "Default")
      (node (ref "U2") (pin "129") (pinfunction "PG14_129") (pintype "bidirectional"))
    )
    (net (code "134") (name "unconnected-(U2B-PG15-Pad132)") (class "Default")
      (node (ref "U2") (pin "132") (pinfunction "PG15_132") (pintype "bidirectional"))
    )
    (net (code "135") (name "unconnected-(U2B-PH0-OSC_IN(PH0)-Pad23)") (class "Default")
      (node (ref "U2") (pin "23") (pinfunction "PH0-OSC_IN(PH0)_23") (pintype "bidirectional"))
    )
    (net (code "136") (name "unconnected-(U2B-PH1-OSC_OUT(PH1)-Pad24)") (class "Default")
      (node (ref "U2") (pin "24") (pinfunction "PH1-OSC_OUT(PH1)_24") (pintype "bidirectional"))
    )
    (net (code "137") (name "unconnected-(U3-EP-Pad17)") (class "Default")
      (node (ref "U3") (pin "17") (pinfunction "EP_17") (pintype "power_in"))
    )
  )
)
